# RF_ant_board.net
KiCad netlist of a schematic drawn in EAGLE
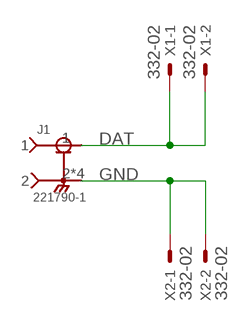
[diagram p0: schematic, sheet 1]

(export (version "E")
  (design (tool "Eeschema 10.0.6"))
  (components
    (comp (ref "J1")
      (value "221790-1")
      (footprint "eagle-import:TE_221790-1")
      (fields (field (name "MF") "TE Connectivity"))
      (libsource (lib "eagle-import") (part "221790-1"))
    )
    (comp (ref "X1")
      (value "332-02")
      (footprint "eagle-import:332-02")
      (libsource (lib "eagle-import") (part "332-02"))
    )
    (comp (ref "X2")
      (value "332-02")
      (footprint "eagle-import:332-02")
      (libsource (lib "eagle-import") (part "332-02"))
    )
  )
  (nets
    (net (code "1") (name "/DAT") (class "Default")
      (node (ref "J1") (pin "1") (pinfunction "1_1") (pintype "passive"))
      (node (ref "X1") (pin "1") (pinfunction "S_1") (pintype "passive"))
      (node (ref "X1") (pin "2") (pinfunction "S_2") (pintype "passive"))
    )
    (net (code "2") (name "/GND") (class "Default")
      (node (ref "J1") (pin "2") (pinfunction "2_2") (pintype "passive"))
      (node (ref "J1") (pin "3") (pinfunction "2_3") (pintype "passive"))
      (node (ref "J1") (pin "4") (pinfunction "2_4") (pintype "passive"))
      (node (ref "J1") (pin "5") (pinfunction "2_5") (pintype "passive"))
      (node (ref "X2") (pin "1") (pinfunction "S_1") (pintype "passive"))
      (node (ref "X2") (pin "2") (pinfunction "S_2") (pintype "passive"))
    )
  )
)
